# CH32V203C8T6-R0.net
KiCad netlist of a schematic drawn in Altium Designer
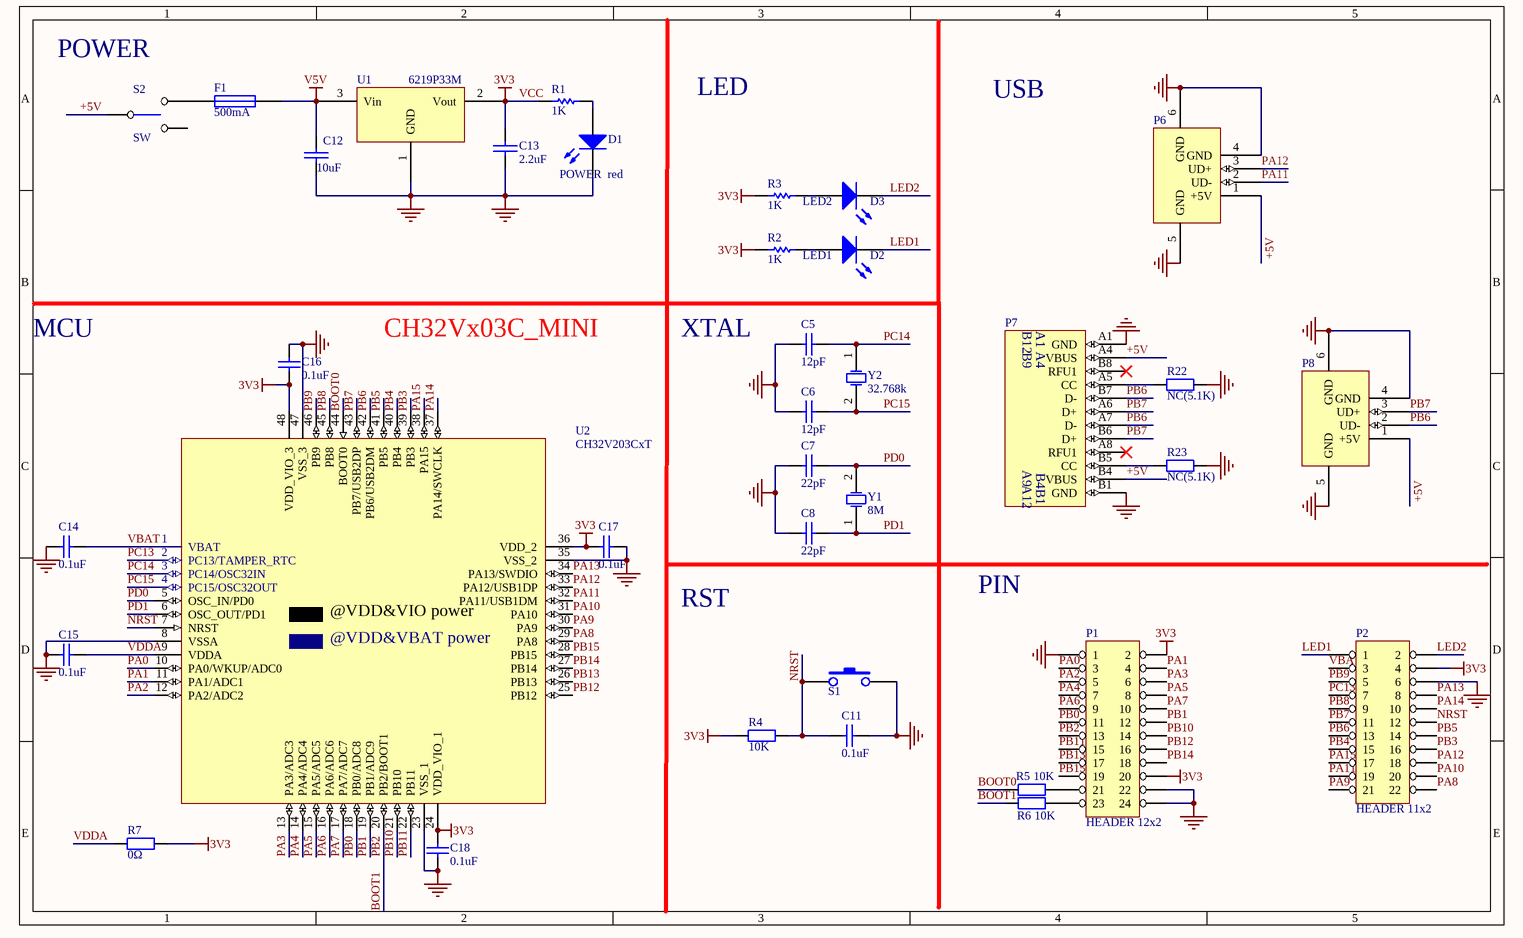
[diagram p0: CH32V203C8T6-R0.SchDoc]

(export (version "E")
  (design (tool "Eeschema 10.0.6"))
  (components
    (comp (ref "C5")
      (value "12pF")
      (footprint "0603_C")
      (description "Capacitor")
      (fields (field (name "PUBLISHER") "Altium Limited"))
      (libsource (lib "*") (part "Cap"))
    )
    (comp (ref "C6")
      (value "12pF")
      (footprint "0603_C")
      (description "Capacitor")
      (fields (field (name "PUBLISHER") "Altium Limited"))
      (libsource (lib "*") (part "Cap"))
    )
    (comp (ref "C7")
      (value "22pF")
      (footprint "0603_C")
      (description "Capacitor")
      (fields (field (name "PUBLISHER") "Altium Limited"))
      (libsource (lib "*") (part "Cap"))
    )
    (comp (ref "C8")
      (value "22pF")
      (footprint "0603_C")
      (description "Capacitor")
      (fields (field (name "PUBLISHER") "Altium Limited"))
      (libsource (lib "*") (part "Cap"))
    )
    (comp (ref "C11")
      (value "0.1uF")
      (footprint "0603_C")
      (description "Capacitor")
      (fields (field (name "PUBLISHER") "Altium Limited"))
      (libsource (lib "*") (part "Cap"))
    )
    (comp (ref "C12")
      (value "10uF")
      (footprint "3216_C")
      (description "Capacitor")
      (libsource (lib "*") (part "CAP"))
    )
    (comp (ref "C13")
      (value "2.2uF")
      (footprint "0603_C")
      (description "Capacitor")
      (libsource (lib "*") (part "CAP"))
    )
    (comp (ref "C14")
      (value "0.1uF")
      (footprint "0603_C")
      (description "Capacitor")
      (fields (field (name "PUBLISHER") "Altium Limited"))
      (libsource (lib "*") (part "Cap"))
    )
    (comp (ref "C15")
      (value "0.1uF")
      (footprint "0603_C")
      (description "Capacitor")
      (fields (field (name "PUBLISHER") "Altium Limited"))
      (libsource (lib "*") (part "Cap"))
    )
    (comp (ref "C16")
      (value "0.1uF")
      (footprint "0603_C")
      (description "Capacitor")
      (fields (field (name "PUBLISHER") "Altium Limited"))
      (libsource (lib "*") (part "Cap"))
    )
    (comp (ref "C17")
      (value "0.1uF")
      (footprint "0603_C")
      (description "Capacitor")
      (fields (field (name "PUBLISHER") "Altium Limited"))
      (libsource (lib "*") (part "Cap"))
    )
    (comp (ref "C18")
      (value "0.1uF")
      (footprint "0603_C")
      (description "Capacitor")
      (fields (field (name "PUBLISHER") "Altium Limited"))
      (libsource (lib "*") (part "Cap"))
    )
    (comp (ref "D1")
      (value "POWER  red")
      (footprint "0603+")
      (description "Typical INFRARED GaAs LED")
      (fields (field (name "PUBLISHER") "Altium Limited"))
      (libsource (lib "*") (part "LED0"))
    )
    (comp (ref "D2")
      (value "LED1")
      (footprint "0603+")
      (description "Typical INFRARED GaAs LED")
      (fields (field (name "PUBLISHER") "Altium Limited"))
      (libsource (lib "*") (part "LED0"))
    )
    (comp (ref "D3")
      (value "LED2")
      (footprint "0603+")
      (description "Typical INFRARED GaAs LED")
      (fields (field (name "PUBLISHER") "Altium Limited"))
      (libsource (lib "*") (part "LED0"))
    )
    (comp (ref "F1")
      (value "500mA")
      (footprint "0603")
      (description "Fuse")
      (libsource (lib "*") (part "FUSE1"))
    )
    (comp (ref "P1")
      (value "HEADER 12x2")
      (footprint "MYPCB:IDC24-2.54MM")
      (description "Header, 12-Pin, Dual row")
      (libsource (lib "wch_sch_others") (part "HEADER 12x2"))
    )
    (comp (ref "P2")
      (value "HEADER 11x2")
      (footprint "MYPCB:IDC22-2.54MM")
      (description "Header, 11-Pin, Dual row")
      (libsource (lib "wch_sch_others") (part "HEADER 11x2"))
    )
    (comp (ref "P6")
      (value "USB_A")
      (footprint "USBAF")
      (description "USB Port")
      (libsource (lib "*") (part "USB"))
    )
    (comp (ref "P7")
      (value "TYPE-C")
      (footprint "TYPE-C-Receptacle-2.0")
      (libsource (lib "*") (part "TYPE-C1"))
    )
    (comp (ref "P8")
      (value "USB_A")
      (footprint "USBAF")
      (description "USB Port")
      (libsource (lib "*") (part "USB"))
    )
    (comp (ref "R1")
      (value "1K")
      (footprint "0603")
      (description "Semiconductor Resistor")
      (fields (field (name "PUBLISHER") "Altium Limited"))
      (libsource (lib "*") (part "Res Semi"))
    )
    (comp (ref "R2")
      (value "1K")
      (footprint "0603")
      (description "Semiconductor Resistor")
      (fields (field (name "PUBLISHER") "Altium Limited"))
      (libsource (lib "*") (part "Res Semi"))
    )
    (comp (ref "R3")
      (value "1K")
      (footprint "0603")
      (description "Semiconductor Resistor")
      (fields (field (name "PUBLISHER") "Altium Limited"))
      (libsource (lib "*") (part "Res Semi"))
    )
    (comp (ref "R4")
      (value "10K")
      (footprint "0603")
      (description "Resistor")
      (fields (field (name "PUBLISHER") "Altium Limited"))
      (libsource (lib "") (part "Res2_1"))
    )
    (comp (ref "R5")
      (value "10K")
      (footprint "0603")
      (description "Resistor")
      (fields (field (name "PUBLISHER") "Altium Limited"))
      (libsource (lib "*") (part "Res2"))
    )
    (comp (ref "R6")
      (value "10K")
      (footprint "0603")
      (description "Resistor")
      (fields (field (name "PUBLISHER") "Altium Limited"))
      (libsource (lib "*") (part "Res2"))
    )
    (comp (ref "R7")
      (value "0Ω")
      (footprint "0603")
      (description "Resistor")
      (fields (field (name "PUBLISHER") "Altium Limited"))
      (libsource (lib "") (part "Res2_1"))
    )
    (comp (ref "R22")
      (value "NC(5.1K)")
      (footprint "0603")
      (description "Resistor")
      (libsource (lib "Miscellaneous Devices") (part "Res2"))
    )
    (comp (ref "R23")
      (value "NC(5.1K)")
      (footprint "0603")
      (description "Resistor")
      (libsource (lib "Miscellaneous Devices") (part "Res2"))
    )
    (comp (ref "S1") (value "KEY") (footprint "贴片按键") (libsource (lib "*") (part "KEY")))
    (comp (ref "S2") (value "SW") (footprint "KEY2") (libsource (lib "*") (part "SW")))
    (comp (ref "U1")
      (value "6219P33M")
      (footprint "SOT-23")
      (libsource (lib "wch_sch_others") (part "6219P33M"))
    )
    (comp (ref "U2")
      (value "CH32V203CxT")
      (footprint "LQFP48")
      (description "RISC-V LMD-MCU, 144MHz, 2*USB FS, CAN")
      (libsource (lib "CHXXX") (part "CH32V203CxT"))
    )
    (comp (ref "Y1")
      (value "8M")
      (footprint "XT_AT49")
      (description "Crystal Oscillator")
      (fields (field (name "PUBLISHER") "Altium Limited"))
      (libsource (lib "*") (part "XTAL"))
    )
    (comp (ref "Y2")
      (value "32.768k")
      (footprint "FC-135")
      (description "Crystal Oscillator")
      (fields (field (name "PUBLISHER") "Altium Limited"))
      (libsource (lib "*") (part "XTAL"))
    )
  )
  (nets
    (net (code "1") (name "/+5V") (class "Default")
      (node (ref "P6") (pin "1") (pinfunction "+5V_1") (pintype "power_in"))
      (node (ref "P7") (pin "A4") (pinfunction "VBUS_A4") (pintype "bidirectional"))
      (node (ref "P7") (pin "B4") (pinfunction "VBUS_B4") (pintype "bidirectional"))
      (node (ref "P8") (pin "1") (pinfunction "+5V_1") (pintype "power_in"))
      (node (ref "S2") (pin "1") (pinfunction "1_1") (pintype "passive"))
    )
    (net (code "3") (name "/BOOT0") (class "Default")
      (node (ref "R5") (pin "1") (pinfunction "1_1") (pintype "passive"))
      (node (ref "U2") (pin "44") (pinfunction "BOOT0_44") (pintype "input"))
    )
    (net (code "4") (name "/BOOT1") (class "Default")
      (node (ref "P1") (pin "13") (pinfunction "13_13") (pintype "passive"))
      (node (ref "R6") (pin "1") (pinfunction "1_1") (pintype "passive"))
      (node (ref "U2") (pin "20") (pinfunction "PB2/BOOT1_20") (pintype "bidirectional"))
    )
    (net (code "5") (name "/LED1") (class "Default")
      (node (ref "D2") (pin "2") (pinfunction "K_2") (pintype "passive"))
      (node (ref "P2") (pin "1") (pinfunction "1_1") (pintype "passive"))
    )
    (net (code "6") (name "/LED2") (class "Default")
      (node (ref "D3") (pin "2") (pinfunction "K_2") (pintype "passive"))
      (node (ref "P2") (pin "2") (pinfunction "2_2") (pintype "passive"))
    )
    (net (code "7") (name "/NRST") (class "Default")
      (node (ref "C11") (pin "2") (pinfunction "2_2") (pintype "passive"))
      (node (ref "P2") (pin "12") (pinfunction "12_12") (pintype "passive"))
      (node (ref "R4") (pin "1") (pinfunction "1_1") (pintype "passive"))
      (node (ref "S1") (pin "1") (pinfunction "1_1") (pintype "passive"))
      (node (ref "U2") (pin "7") (pinfunction "NRST_7") (pintype "input"))
    )
    (net (code "8") (name "/PA0") (class "Default")
      (node (ref "P1") (pin "3") (pinfunction "3_3") (pintype "passive"))
      (node (ref "U2") (pin "10") (pinfunction "PA0/WKUP/ADC0_10") (pintype "bidirectional"))
    )
    (net (code "9") (name "/PA1") (class "Default")
      (node (ref "P1") (pin "4") (pinfunction "4_4") (pintype "passive"))
      (node (ref "U2") (pin "11") (pinfunction "PA1/ADC1_11") (pintype "bidirectional"))
    )
    (net (code "10") (name "/PA2") (class "Default")
      (node (ref "P1") (pin "5") (pinfunction "5_5") (pintype "passive"))
      (node (ref "U2") (pin "12") (pinfunction "PA2/ADC2_12") (pintype "bidirectional"))
    )
    (net (code "11") (name "/PA3") (class "Default")
      (node (ref "P1") (pin "6") (pinfunction "6_6") (pintype "passive"))
      (node (ref "U2") (pin "13") (pinfunction "PA3/ADC3_13") (pintype "bidirectional"))
    )
    (net (code "12") (name "/PA4") (class "Default")
      (node (ref "P1") (pin "7") (pinfunction "7_7") (pintype "passive"))
      (node (ref "U2") (pin "14") (pinfunction "PA4/ADC4_14") (pintype "bidirectional"))
    )
    (net (code "13") (name "/PA5") (class "Default")
      (node (ref "P1") (pin "8") (pinfunction "8_8") (pintype "passive"))
      (node (ref "U2") (pin "15") (pinfunction "PA5/ADC5_15") (pintype "bidirectional"))
    )
    (net (code "14") (name "/PA6") (class "Default")
      (node (ref "P1") (pin "9") (pinfunction "9_9") (pintype "passive"))
      (node (ref "U2") (pin "16") (pinfunction "PA6/ADC6_16") (pintype "bidirectional"))
    )
    (net (code "15") (name "/PA7") (class "Default")
      (node (ref "P1") (pin "10") (pinfunction "10_10") (pintype "passive"))
      (node (ref "U2") (pin "17") (pinfunction "PA7/ADC7_17") (pintype "bidirectional"))
    )
    (net (code "16") (name "/PA8") (class "Default")
      (node (ref "P2") (pin "22") (pinfunction "22_22") (pintype "passive"))
      (node (ref "U2") (pin "29") (pinfunction "PA8_29") (pintype "bidirectional"))
    )
    (net (code "17") (name "/PA9") (class "Default")
      (node (ref "P2") (pin "21") (pinfunction "21_21") (pintype "passive"))
      (node (ref "U2") (pin "30") (pinfunction "PA9_30") (pintype "bidirectional"))
    )
    (net (code "18") (name "/PA10") (class "Default")
      (node (ref "P2") (pin "20") (pinfunction "20_20") (pintype "passive"))
      (node (ref "U2") (pin "31") (pinfunction "PA10_31") (pintype "bidirectional"))
    )
    (net (code "19") (name "/PA11") (class "Default")
      (node (ref "P2") (pin "19") (pinfunction "19_19") (pintype "passive"))
      (node (ref "P6") (pin "2") (pinfunction "UD-_2") (pintype "bidirectional"))
      (node (ref "U2") (pin "32") (pinfunction "PA11/USB1DM_32") (pintype "bidirectional"))
    )
    (net (code "20") (name "/PA12") (class "Default")
      (node (ref "P2") (pin "18") (pinfunction "18_18") (pintype "passive"))
      (node (ref "P6") (pin "3") (pinfunction "UD+_3") (pintype "bidirectional"))
      (node (ref "U2") (pin "33") (pinfunction "PA12/USB1DP_33") (pintype "bidirectional"))
    )
    (net (code "21") (name "/PA13") (class "Default")
      (node (ref "P2") (pin "8") (pinfunction "8_8") (pintype "passive"))
      (node (ref "U2") (pin "34") (pinfunction "PA13/SWDIO_34") (pintype "bidirectional"))
    )
    (net (code "22") (name "/PA14") (class "Default")
      (node (ref "P2") (pin "10") (pinfunction "10_10") (pintype "passive"))
      (node (ref "U2") (pin "37") (pinfunction "PA14/SWCLK_37") (pintype "bidirectional"))
    )
    (net (code "23") (name "/PA15") (class "Default")
      (node (ref "P2") (pin "17") (pinfunction "17_17") (pintype "passive"))
      (node (ref "U2") (pin "38") (pinfunction "PA15_38") (pintype "bidirectional"))
    )
    (net (code "24") (name "/PB0") (class "Default")
      (node (ref "P1") (pin "11") (pinfunction "11_11") (pintype "passive"))
      (node (ref "U2") (pin "18") (pinfunction "PB0/ADC8_18") (pintype "bidirectional"))
    )
    (net (code "25") (name "/PB1") (class "Default")
      (node (ref "P1") (pin "12") (pinfunction "12_12") (pintype "passive"))
      (node (ref "U2") (pin "19") (pinfunction "PB1/ADC9_19") (pintype "bidirectional"))
    )
    (net (code "26") (name "/PB3") (class "Default")
      (node (ref "P2") (pin "16") (pinfunction "16_16") (pintype "passive"))
      (node (ref "U2") (pin "39") (pinfunction "PB3_39") (pintype "bidirectional"))
    )
    (net (code "27") (name "/PB4") (class "Default")
      (node (ref "P2") (pin "15") (pinfunction "15_15") (pintype "passive"))
      (node (ref "U2") (pin "40") (pinfunction "PB4_40") (pintype "bidirectional"))
    )
    (net (code "28") (name "/PB5") (class "Default")
      (node (ref "P2") (pin "14") (pinfunction "14_14") (pintype "passive"))
      (node (ref "U2") (pin "41") (pinfunction "PB5_41") (pintype "bidirectional"))
    )
    (net (code "29") (name "/PB6") (class "Default")
      (node (ref "P2") (pin "13") (pinfunction "13_13") (pintype "passive"))
      (node (ref "P7") (pin "A7") (pinfunction "D-_A7") (pintype "bidirectional"))
      (node (ref "P7") (pin "B7") (pinfunction "D-_B7") (pintype "bidirectional"))
      (node (ref "P8") (pin "2") (pinfunction "UD-_2") (pintype "bidirectional"))
      (node (ref "U2") (pin "42") (pinfunction "PB6/USB2DM_42") (pintype "bidirectional"))
    )
    (net (code "30") (name "/PB7") (class "Default")
      (node (ref "P2") (pin "11") (pinfunction "11_11") (pintype "passive"))
      (node (ref "P7") (pin "A6") (pinfunction "D+_A6") (pintype "bidirectional"))
      (node (ref "P7") (pin "B6") (pinfunction "D+_B6") (pintype "bidirectional"))
      (node (ref "P8") (pin "3") (pinfunction "UD+_3") (pintype "bidirectional"))
      (node (ref "U2") (pin "43") (pinfunction "PB7/USB2DP_43") (pintype "bidirectional"))
    )
    (net (code "31") (name "/PB8") (class "Default")
      (node (ref "P2") (pin "9") (pinfunction "9_9") (pintype "passive"))
      (node (ref "U2") (pin "45") (pinfunction "PB8_45") (pintype "bidirectional"))
    )
    (net (code "32") (name "/PB9") (class "Default")
      (node (ref "P2") (pin "5") (pinfunction "5_5") (pintype "passive"))
      (node (ref "U2") (pin "46") (pinfunction "PB9_46") (pintype "bidirectional"))
    )
    (net (code "33") (name "/PB10") (class "Default")
      (node (ref "P1") (pin "14") (pinfunction "14_14") (pintype "passive"))
      (node (ref "U2") (pin "21") (pinfunction "PB10_21") (pintype "bidirectional"))
    )
    (net (code "34") (name "/PB11") (class "Default")
      (node (ref "P1") (pin "15") (pinfunction "15_15") (pintype "passive"))
      (node (ref "U2") (pin "22") (pinfunction "PB11_22") (pintype "bidirectional"))
    )
    (net (code "35") (name "/PB12") (class "Default")
      (node (ref "P1") (pin "16") (pinfunction "16_16") (pintype "passive"))
      (node (ref "U2") (pin "25") (pinfunction "PB12_25") (pintype "bidirectional"))
    )
    (net (code "36") (name "/PB13") (class "Default")
      (node (ref "P1") (pin "17") (pinfunction "17_17") (pintype "passive"))
      (node (ref "U2") (pin "26") (pinfunction "PB13_26") (pintype "bidirectional"))
    )
    (net (code "37") (name "/PB14") (class "Default")
      (node (ref "P1") (pin "18") (pinfunction "18_18") (pintype "passive"))
      (node (ref "U2") (pin "27") (pinfunction "PB14_27") (pintype "bidirectional"))
    )
    (net (code "38") (name "/PB15") (class "Default")
      (node (ref "P1") (pin "19") (pinfunction "19_19") (pintype "passive"))
      (node (ref "U2") (pin "28") (pinfunction "PB15_28") (pintype "bidirectional"))
    )
    (net (code "39") (name "/PC13") (class "Default")
      (node (ref "P2") (pin "7") (pinfunction "7_7") (pintype "passive"))
      (node (ref "U2") (pin "2") (pinfunction "PC13/TAMPER_RTC_2") (pintype "bidirectional"))
    )
    (net (code "40") (name "/PC14") (class "Default")
      (node (ref "C5") (pin "1") (pinfunction "1_1") (pintype "passive"))
      (node (ref "U2") (pin "3") (pinfunction "PC14/OSC32IN_3") (pintype "bidirectional"))
      (node (ref "Y2") (pin "1") (pinfunction "OSC1_1") (pintype "passive"))
    )
    (net (code "41") (name "/PC15") (class "Default")
      (node (ref "C6") (pin "1") (pinfunction "1_1") (pintype "passive"))
      (node (ref "U2") (pin "4") (pinfunction "PC15/OSC32OUT_4") (pintype "bidirectional"))
      (node (ref "Y2") (pin "2") (pinfunction "OSC2_2") (pintype "passive"))
    )
    (net (code "42") (name "/PD0") (class "Default")
      (node (ref "C7") (pin "2") (pinfunction "2_2") (pintype "passive"))
      (node (ref "U2") (pin "5") (pinfunction "OSC_IN/PD0_5") (pintype "bidirectional"))
      (node (ref "Y1") (pin "2") (pinfunction "OSC2_2") (pintype "passive"))
    )
    (net (code "43") (name "/PD1") (class "Default")
      (node (ref "C8") (pin "2") (pinfunction "2_2") (pintype "passive"))
      (node (ref "U2") (pin "6") (pinfunction "OSC_OUT/PD1_6") (pintype "bidirectional"))
      (node (ref "Y1") (pin "1") (pinfunction "OSC1_1") (pintype "passive"))
    )
    (net (code "44") (name "/VBAT") (class "Default")
      (node (ref "C14") (pin "1") (pinfunction "1_1") (pintype "passive"))
      (node (ref "P2") (pin "3") (pinfunction "3_3") (pintype "passive"))
      (node (ref "U2") (pin "1") (pinfunction "VBAT_1") (pintype "power_in"))
    )
    (net (code "45") (name "/VDDA") (class "Default")
      (node (ref "C15") (pin "1") (pinfunction "1_1") (pintype "passive"))
      (node (ref "R7") (pin "2") (pinfunction "2_2") (pintype "passive"))
      (node (ref "U2") (pin "9") (pinfunction "VDDA_9") (pintype "power_in"))
    )
    (net (code "46") (name "3V3") (class "Default")
      (node (ref "C13") (pin "1") (pinfunction "1_1") (pintype "passive"))
      (node (ref "C16") (pin "2") (pinfunction "2_2") (pintype "passive"))
      (node (ref "C17") (pin "2") (pinfunction "2_2") (pintype "passive"))
      (node (ref "C18") (pin "2") (pinfunction "2_2") (pintype "passive"))
      (node (ref "P1") (pin "2") (pinfunction "2_2") (pintype "passive"))
      (node (ref "P1") (pin "20") (pinfunction "20_20") (pintype "passive"))
      (node (ref "P2") (pin "4") (pinfunction "4_4") (pintype "passive"))
      (node (ref "R1") (pin "2") (pinfunction "2_2") (pintype "passive"))
      (node (ref "R2") (pin "1") (pinfunction "1_1") (pintype "passive"))
      (node (ref "R3") (pin "1") (pinfunction "1_1") (pintype "passive"))
      (node (ref "R4") (pin "2") (pinfunction "2_2") (pintype "passive"))
      (node (ref "R7") (pin "1") (pinfunction "1_1") (pintype "passive"))
      (node (ref "U1") (pin "2") (pinfunction "Vout_2") (pintype "passive"))
      (node (ref "U2") (pin "24") (pinfunction "VDD_VIO_1_24") (pintype "power_in"))
      (node (ref "U2") (pin "36") (pinfunction "VDD_2_36") (pintype "power_in"))
      (node (ref "U2") (pin "48") (pinfunction "VDD_VIO_3_48") (pintype "power_in"))
    )
    (net (code "47") (name "GND") (class "Default")
      (node (ref "C11") (pin "1") (pinfunction "1_1") (pintype "passive"))
      (node (ref "C12") (pin "2") (pinfunction "2_2") (pintype "passive"))
      (node (ref "C13") (pin "2") (pinfunction "2_2") (pintype "passive"))
      (node (ref "C14") (pin "2") (pinfunction "2_2") (pintype "passive"))
      (node (ref "C15") (pin "2") (pinfunction "2_2") (pintype "passive"))
      (node (ref "C16") (pin "1") (pinfunction "1_1") (pintype "passive"))
      (node (ref "C17") (pin "1") (pinfunction "1_1") (pintype "passive"))
      (node (ref "C18") (pin "1") (pinfunction "1_1") (pintype "passive"))
      (node (ref "C5") (pin "2") (pinfunction "2_2") (pintype "passive"))
      (node (ref "C6") (pin "2") (pinfunction "2_2") (pintype "passive"))
      (node (ref "C7") (pin "1") (pinfunction "1_1") (pintype "passive"))
      (node (ref "C8") (pin "1") (pinfunction "1_1") (pintype "passive"))
      (node (ref "D1") (pin "2") (pinfunction "K_2") (pintype "passive"))
      (node (ref "P1") (pin "1") (pinfunction "1_1") (pintype "passive"))
      (node (ref "P1") (pin "22") (pinfunction "22_22") (pintype "passive"))
      (node (ref "P1") (pin "24") (pinfunction "24_24") (pintype "passive"))
      (node (ref "P2") (pin "6") (pinfunction "6_6") (pintype "passive"))
      (node (ref "P6") (pin "4") (pinfunction "GND_4") (pintype "power_in"))
      (node (ref "P6") (pin "5") (pinfunction "GND_5") (pintype "power_in"))
      (node (ref "P6") (pin "6") (pinfunction "GND_6") (pintype "power_in"))
      (node (ref "P7") (pin "A1") (pinfunction "GND_A1") (pintype "bidirectional"))
      (node (ref "P7") (pin "B1") (pinfunction "GND_B1") (pintype "bidirectional"))
      (node (ref "P8") (pin "4") (pinfunction "GND_4") (pintype "power_in"))
      (node (ref "P8") (pin "5") (pinfunction "GND_5") (pintype "power_in"))
      (node (ref "P8") (pin "6") (pinfunction "GND_6") (pintype "power_in"))
      (node (ref "R22") (pin "2") (pinfunction "2_2") (pintype "passive"))
      (node (ref "R23") (pin "2") (pinfunction "2_2") (pintype "passive"))
      (node (ref "S1") (pin "2") (pinfunction "2_2") (pintype "passive"))
      (node (ref "U1") (pin "1") (pinfunction "GND_1") (pintype "passive"))
      (node (ref "U2") (pin "23") (pinfunction "VSS_1_23") (pintype "power_in"))
      (node (ref "U2") (pin "35") (pinfunction "VSS_2_35") (pintype "power_in"))
      (node (ref "U2") (pin "47") (pinfunction "VSS_3_47") (pintype "power_in"))
      (node (ref "U2") (pin "8") (pinfunction "VSSA_8") (pintype "power_in"))
    )
    (net (code "48") (name "Net-(D1-A)") (class "Default")
      (node (ref "D1") (pin "1") (pinfunction "A_1") (pintype "passive"))
      (node (ref "R1") (pin "1") (pinfunction "1_1") (pintype "passive"))
    )
    (net (code "49") (name "Net-(D2-A)") (class "Default")
      (node (ref "D2") (pin "1") (pinfunction "A_1") (pintype "passive"))
      (node (ref "R2") (pin "2") (pinfunction "2_2") (pintype "passive"))
    )
    (net (code "50") (name "Net-(D3-A)") (class "Default")
      (node (ref "D3") (pin "1") (pinfunction "A_1") (pintype "passive"))
      (node (ref "R3") (pin "2") (pinfunction "2_2") (pintype "passive"))
    )
    (net (code "51") (name "Net-(F1-Pad1)") (class "Default")
      (node (ref "F1") (pin "1") (pinfunction "1_1") (pintype "passive"))
      (node (ref "S2") (pin "3") (pinfunction "3_3") (pintype "passive"))
    )
    (net (code "52") (name "Net-(P1-Pad21)") (class "Default")
      (node (ref "P1") (pin "21") (pinfunction "21_21") (pintype "passive"))
      (node (ref "R5") (pin "2") (pinfunction "2_2") (pintype "passive"))
    )
    (net (code "53") (name "Net-(P1-Pad23)") (class "Default")
      (node (ref "P1") (pin "23") (pinfunction "23_23") (pintype "passive"))
      (node (ref "R6") (pin "2") (pinfunction "2_2") (pintype "passive"))
    )
    (net (code "54") (name "Net-(P7-CC-PadA5)") (class "Default")
      (node (ref "P7") (pin "A5") (pinfunction "CC_A5") (pintype "bidirectional"))
      (node (ref "R22") (pin "1") (pinfunction "1_1") (pintype "passive"))
    )
    (net (code "55") (name "Net-(P7-CC-PadB5)") (class "Default")
      (node (ref "P7") (pin "B5") (pinfunction "CC_B5") (pintype "bidirectional"))
      (node (ref "R23") (pin "1") (pinfunction "1_1") (pintype "passive"))
    )
    (net (code "56") (name "V5V") (class "Default")
      (node (ref "C12") (pin "1") (pinfunction "1_1") (pintype "passive"))
      (node (ref "F1") (pin "2") (pinfunction "2_2") (pintype "passive"))
      (node (ref "U1") (pin "3") (pinfunction "Vin_3") (pintype "passive"))
    )
    (net (code "57") (name "unconnected-(P7-RFU1-PadA8)") (class "Default")
      (node (ref "P7") (pin "A8") (pinfunction "RFU1_A8") (pintype "bidirectional+no_connect"))
    )
    (net (code "58") (name "unconnected-(P7-RFU1-PadB8)") (class "Default")
      (node (ref "P7") (pin "B8") (pinfunction "RFU1_B8") (pintype "bidirectional+no_connect"))
    )
    (net (code "59") (name "unconnected-(S2-Pad2)") (class "Default")
      (node (ref "S2") (pin "2") (pinfunction "2_2") (pintype "passive"))
    )
  )
)
